# 15ACurrentSensor.net
KiCad netlist of a schematic drawn in Altium Designer
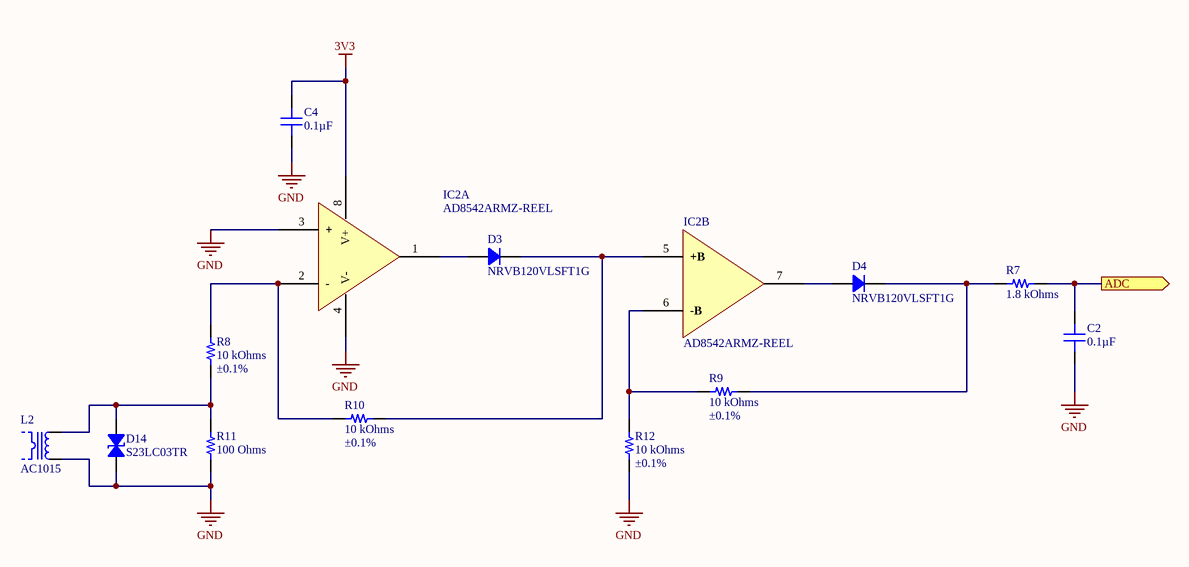
[diagram p0: 15ACurrentSensor.SchDoc]

(export (version "E")
  (design (tool "Eeschema 10.0.6"))
  (components
    (comp (ref "C2")
      (value "0.1µF")
      (footprint "CAP 0603_1608")
      (description "CAP CER 0.1UF 16V X7R 0603")
      (fields (field (name "PART NUMBER") "CS0603KRX7R7BB104") (field (name "MANUFACTURER") "Yageo"))
      (libsource (lib "Celestial Altium Library - altium_library") (part "Capacitor"))
    )
    (comp (ref "C4")
      (value "0.1µF")
      (footprint "CAP 0603_1608")
      (description "CAP CER 0.1UF 16V X7R 0603")
      (fields (field (name "PART NUMBER") "CS0603KRX7R7BB104") (field (name "MANUFACTURER") "Yageo"))
      (libsource (lib "Celestial Altium Library - altium_library") (part "Capacitor"))
    )
    (comp (ref "D3")
      (value "NRVB120VLSFT1G")
      (footprint "SOD123F")
      (description "DIODE SCHOTTKY 20V 1A SOD123")
      (fields (field (name "MANUFACTURER") "ON Semiconductor"))
      (libsource (lib "Celestial Altium Library - altium_library") (part "Diode"))
    )
    (comp (ref "D4")
      (value "NRVB120VLSFT1G")
      (footprint "SOD123F")
      (description "DIODE SCHOTTKY 20V 1A SOD123")
      (fields (field (name "MANUFACTURER") "ON Semiconductor"))
      (libsource (lib "Celestial Altium Library - altium_library") (part "Diode"))
    )
    (comp (ref "D14")
      (value "S23LC03TR")
      (footprint "DIODES SOT-23-3")
      (description "TVS DIODE 3.3V 8V SOT23")
      (fields (field (name "MANUFACTURER") "SMC Diode Solutions"))
      (libsource (lib "Celestial Altium Library - altium_library") (part "Diode TVS"))
    )
    (comp (ref "IC2")
      (value "AD8542ARMZ-REEL")
      (footprint "ANALOG MSOP-8 RM-8")
      (description "IC OPAMP GP 2 CIRCUIT 8MSOP")
      (fields (field (name "MANUFACTURER") "Analog Devices Inc."))
      (libsource (lib "Celestial Altium Library - altium_library") (part "ANALOG DEV AD8542"))
    )
    (comp (ref "L2")
      (value "AC1015")
      (footprint "TALEMA AC1015")
      (description "CURR SENSE XFMR 15A T/H")
      (fields (field (name "MANUFACTURER") "Talema Group LLC"))
      (libsource (lib "Celestial Altium Library - altium_library") (part "TALEMA AC1xxx"))
    )
    (comp (ref "R7")
      (value "1.8 kOhms")
      (footprint "RES 0603_1608")
      (description "RES 1.8K OHM 5% 1/10W 0603")
      (fields
        (field (name "PART NUMBER") "RMCF0603JT1K80")
        (field (name "MANUFACTURER") "Stackpole Electronics Inc")
      )
      (libsource (lib "Celestial Altium Library - altium_library") (part "Resistor"))
    )
    (comp (ref "R8")
      (value "10 kOhms")
      (footprint "RES 0603_1608")
      (description "RES SMD 10K OHM 0.1% 1/10W 0603")
      (fields
        (field (name "PART NUMBER") "ERA-3AEB103V")
        (field (name "MANUFACTURER") "Panasonic Electronic Components")
        (field (name "TOLERANCE") "±0.1%")
      )
      (libsource (lib "Celestial Altium Library - altium_library") (part "Resistor"))
    )
    (comp (ref "R9")
      (value "10 kOhms")
      (footprint "RES 0603_1608")
      (description "RES SMD 10K OHM 0.1% 1/10W 0603")
      (fields
        (field (name "PART NUMBER") "ERA-3AEB103V")
        (field (name "MANUFACTURER") "Panasonic Electronic Components")
        (field (name "TOLERANCE") "±0.1%")
      )
      (libsource (lib "Celestial Altium Library - altium_library") (part "Resistor"))
    )
    (comp (ref "R10")
      (value "10 kOhms")
      (footprint "RES 0603_1608")
      (description "RES SMD 10K OHM 0.1% 1/10W 0603")
      (fields
        (field (name "PART NUMBER") "ERA-3AEB103V")
        (field (name "MANUFACTURER") "Panasonic Electronic Components")
        (field (name "TOLERANCE") "±0.1%")
      )
      (libsource (lib "Celestial Altium Library - altium_library") (part "Resistor"))
    )
    (comp (ref "R11")
      (value "100 Ohms")
      (footprint "RES 0603_1608")
      (description "RES SMD 100 OHM 5% 1/4W 0603")
      (fields (field (name "PART NUMBER") "ESR03EZPJ101") (field (name "MANUFACTURER") "Rohm Semiconductor"))
      (libsource (lib "Celestial Altium Library - altium_library") (part "Resistor"))
    )
    (comp (ref "R12")
      (value "10 kOhms")
      (footprint "RES 0603_1608")
      (description "RES SMD 10K OHM 0.1% 1/10W 0603")
      (fields
        (field (name "PART NUMBER") "ERA-3AEB103V")
        (field (name "MANUFACTURER") "Panasonic Electronic Components")
        (field (name "TOLERANCE") "±0.1%")
      )
      (libsource (lib "Celestial Altium Library - altium_library") (part "Resistor"))
    )
  )
  (nets
    (net (code "1") (name "/ADC") (class "Default")
      (node (ref "C2") (pin "2") (pinfunction "2_2") (pintype "passive"))
      (node (ref "R7") (pin "2") (pinfunction "2_2") (pintype "passive"))
    )
    (net (code "2") (name "3V3") (class "Default")
      (node (ref "C4") (pin "2") (pinfunction "2_2") (pintype "passive"))
      (node (ref "IC2") (pin "8") (pinfunction "V+_8") (pintype "passive"))
    )
    (net (code "3") (name "GND") (class "Default")
      (node (ref "C2") (pin "1") (pinfunction "1_1") (pintype "passive"))
      (node (ref "C4") (pin "1") (pinfunction "1_1") (pintype "passive"))
      (node (ref "D14") (pin "1") (pinfunction "1_1") (pintype "passive"))
      (node (ref "IC2") (pin "3") (pinfunction "+_3") (pintype "passive"))
      (node (ref "IC2") (pin "4") (pinfunction "V-_4") (pintype "passive"))
      (node (ref "L2") (pin "1") (pinfunction "1_1") (pintype "passive"))
      (node (ref "R11") (pin "1") (pinfunction "1_1") (pintype "passive"))
      (node (ref "R12") (pin "2") (pinfunction "2_2") (pintype "passive"))
    )
    (net (code "4") (name "Net-(D4-Pad2)") (class "Default")
      (node (ref "D4") (pin "2") (pinfunction "2_2") (pintype "passive"))
      (node (ref "R7") (pin "1") (pinfunction "1_1") (pintype "passive"))
      (node (ref "R9") (pin "1") (pinfunction "1_1") (pintype "passive"))
    )
    (net (code "5") (name "Net-(D14-Pad2)") (class "Default")
      (node (ref "D14") (pin "2") (pinfunction "2_2") (pintype "passive"))
      (node (ref "L2") (pin "2") (pinfunction "2_2") (pintype "passive"))
      (node (ref "R11") (pin "2") (pinfunction "2_2") (pintype "passive"))
      (node (ref "R8") (pin "1") (pinfunction "1_1") (pintype "passive"))
    )
    (net (code "6") (name "Net-(IC2A--)") (class "Default")
      (node (ref "IC2") (pin "2") (pinfunction "-_2") (pintype "passive"))
      (node (ref "R10") (pin "2") (pinfunction "2_2") (pintype "passive"))
      (node (ref "R8") (pin "2") (pinfunction "2_2") (pintype "passive"))
    )
    (net (code "7") (name "Net-(IC2A-OUT)") (class "Default")
      (node (ref "D3") (pin "1") (pinfunction "1_1") (pintype "passive"))
      (node (ref "IC2") (pin "1") (pinfunction "OUT_1") (pintype "passive"))
    )
    (net (code "8") (name "Net-(IC2B-+B)") (class "Default")
      (node (ref "D3") (pin "2") (pinfunction "2_2") (pintype "passive"))
      (node (ref "IC2") (pin "5") (pinfunction "+B_5") (pintype "passive"))
      (node (ref "R10") (pin "1") (pinfunction "1_1") (pintype "passive"))
    )
    (net (code "9") (name "Net-(IC2B--B)") (class "Default")
      (node (ref "IC2") (pin "6") (pinfunction "-B_6") (pintype "passive"))
      (node (ref "R12") (pin "1") (pinfunction "1_1") (pintype "passive"))
      (node (ref "R9") (pin "2") (pinfunction "2_2") (pintype "passive"))
    )
    (net (code "10") (name "Net-(IC2B-OUT_B)") (class "Default")
      (node (ref "D4") (pin "1") (pinfunction "1_1") (pintype "passive"))
      (node (ref "IC2") (pin "7") (pinfunction "OUT_B_7") (pintype "passive"))
    )
  )
)
